# circuit.net
KiCad netlist of a schematic drawn in Altium Designer
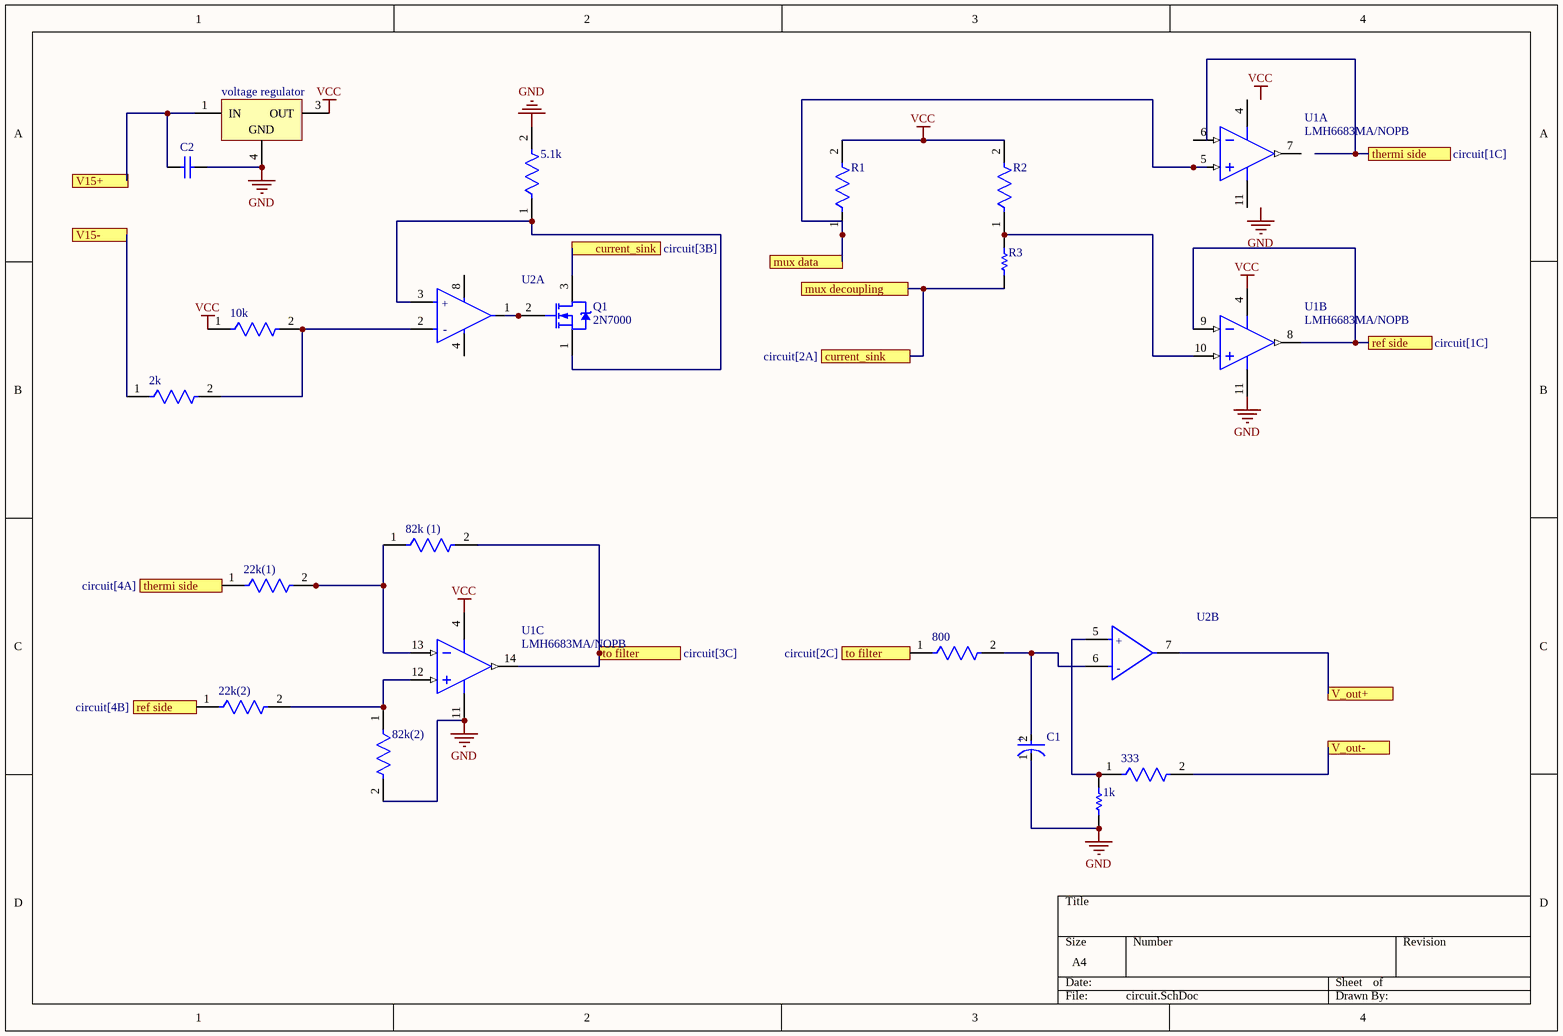
[diagram p0: circuit.SchDoc]

(export (version "E")
  (design (tool "Eeschema 10.0.6"))
  (components
    (comp (ref "1k")
      (value "CRCW12101K00FKEAHP")
      (footprint "RESC3225X60X45NL20T20")
      (fields (field (name "MANUFACTURER") "Vishay Dale"))
      (libsource (lib "Altium Content Vault") (part "RES"))
    )
    (comp (ref "2k")
      (value "CRCW12062K00FKEA")
      (footprint "FP-CRCW1206-e3-IPC_A")
      (description "RES Thick Film, 2kΩ, 1%, 0.25W, 100ppm/°C, 1206")
      (fields (field (name "TOLERANCE") "1%"))
      (libsource (lib "Altium Content Vault") (part "1029c3af85768c4190bb7ad29bc67b5"))
    )
    (comp (ref "5.1k")
      (value "CRCW12065K10FKEA")
      (footprint "FP-CRCW1206-e3-IPC_C")
      (description "RES Thick Film, 5.1kΩ, 1%, 0.25W, 100ppm/°C, 1206")
      (fields (field (name "TOLERANCE") "1%"))
      (libsource (lib "Altium Content Vault") (part "1029c3af85768c4190bb7ad29bc67b5"))
    )
    (comp (ref "10k")
      (value "CRCW120610K0FKEA")
      (footprint "FP-CRCW1206-e3-IPC_C")
      (description "RES Thick Film, 10kΩ, 1%, 0.25W, 100ppm/°C, 1206")
      (fields (field (name "TOLERANCE") "1%"))
      (libsource (lib "Altium Content Vault") (part "1029c3af85768c4190bb7ad29bc67b5"))
    )
    (comp (ref "22k(1)")
      (value "CRCW120622K0FKEA")
      (footprint "FP-CRCW1206-e3-IPC_A")
      (description "RES Thick Film, 22kΩ, 1%, 0.25W, 100ppm/°C, 1206")
      (fields (field (name "TOLERANCE") "1%"))
      (libsource (lib "Altium Content Vault") (part "1029c3af85768c4190bb7ad29bc67b5"))
    )
    (comp (ref "22k(2)")
      (value "CRCW120622K0FKEA")
      (footprint "FP-CRCW1206-e3-IPC_A")
      (description "RES Thick Film, 22kΩ, 1%, 0.25W, 100ppm/°C, 1206")
      (fields (field (name "TOLERANCE") "1%"))
      (libsource (lib "Altium Content Vault") (part "1029c3af85768c4190bb7ad29bc67b5"))
    )
    (comp (ref "82k (1)")
      (value "CRCW120682K0FKEA")
      (footprint "FP-CRCW1206-e3-IPC_B")
      (description "RES Thick Film, 82kΩ, 1%, 0.25W, 100ppm/°C, 1206")
      (fields (field (name "TOLERANCE") "1%"))
      (libsource (lib "Altium Content Vault") (part "1029c3af85768c4190bb7ad29bc67b5"))
    )
    (comp (ref "82k(2)")
      (value "CRCW120682K0FKEA")
      (footprint "FP-CRCW1206-e3-IPC_B")
      (description "RES Thick Film, 82kΩ, 1%, 0.25W, 100ppm/°C, 1206")
      (fields (field (name "TOLERANCE") "1%"))
      (libsource (lib "Altium Content Vault") (part "1029c3af85768c4190bb7ad29bc67b5"))
    )
    (comp (ref "333")
      (value "CRCW0603330RFKEAHP")
      (footprint "FP-CRCW0603-HPe3-IPC_C")
      (description "RES Thick Film, 330Ω, 1%, 0.33W, 100ppm/°C, 0603")
      (fields (field (name "TOLERANCE") "1%"))
      (libsource (lib "Altium Content Vault") (part "1029c3af85768c4190bb7ad29bc67b5"))
    )
    (comp (ref "800")
      (value "MCA12060D8000BP500")
      (footprint "FP-MCA1206-IPC_C")
      (description "Res MC Precision Thin Film 1206 800Ω 0.1% 0.25W ±25ppm/°C Molded Paper T/R")
      (fields (field (name "TOLERANCE") "0.1%"))
      (libsource (lib "Altium Content Vault") (part "1029c3af85768c4190bb7ad29bc67b5"))
    )
    (comp (ref "C1")
      (value "TAJA106K016RNJ")
      (footprint "FP-TAJA-MFG")
      (description "10uF 16V  ±10% 3Ω 1206  SMD Tantalum Capacitor")
      (fields (field (name "VOLTAGE") "16V") (field (name "TOLERANCE") "10%"))
      (libsource (lib "Altium Content Vault") (part "203bc49f2ac43e59fd269a8c329ed05"))
    )
    (comp (ref "C2")
      (value "GRM188R61E105KA12D")
      (footprint "CAPC1608X90X35LL10T15")
      (fields (field (name "MANUFACTURER") "Murata"))
      (libsource (lib "Altium Content Vault") (part "CAP"))
    )
    (comp (ref "Q1")
      (value "2N7000")
      (footprint "ONSC-TO-92-3-29-11")
      (description "Small Signal MOSFET, 200 mA, 60 V, N-Channel, 3-Pin TO-92, Bulk Box")
      (fields (field (name "MANUFACTURER") "On Semiconductor"))
      (libsource (lib "Altium Content Vault") (part "ONSC-NMOS-S1G2D3-3"))
    )
    (comp (ref "R1")
      (value "CRCW120633K0FKEA")
      (footprint "FP-CRCW1206-e3-IPC_B")
      (description "RES Thick Film, 33kΩ, 1%, 0.25W, 100ppm/°C, 1206")
      (fields (field (name "TOLERANCE") "1%"))
      (libsource (lib "Altium Content Vault") (part "1029c3af85768c4190bb7ad29bc67b5"))
    )
    (comp (ref "R2")
      (value "CRCW120633K0FKEA")
      (footprint "FP-CRCW1206-e3-IPC_B")
      (description "RES Thick Film, 33kΩ, 1%, 0.25W, 100ppm/°C, 1206")
      (fields (field (name "TOLERANCE") "1%"))
      (libsource (lib "Altium Content Vault") (part "1029c3af85768c4190bb7ad29bc67b5"))
    )
    (comp (ref "R3")
      (value "CRCW120615K0FKEA")
      (footprint "RESC3216X60X45LL10T20")
      (fields (field (name "MANUFACTURER") "Vishay Dale"))
      (libsource (lib "Altium Content Vault") (part "RES"))
    )
    (comp (ref "U1")
      (value "LMH6683MA/NOPB")
      (footprint "D0014A_M")
      (description "190MHz Single Supply, Dual and Triple Operational Amplifiers, 14-pin Narrow SOIC, Pb-Free")
      (fields (field (name "MANUFACTURER") "Texas Instruments"))
      (libsource (lib "Altium Content Vault") (part "AMP-OPA-LMH6683-14"))
    )
    (comp (ref "U2")
      (value "LM2904DGKR")
      (footprint "FP-DGK0008A-IPC_B")
      (description "IC OPAMP GP 2 CIRCUIT 8VSSOP")
      (libsource (lib "Altium Content Vault") (part "2a1159f5a9c9187fae0bca0d6f85a37"))
    )
    (comp (ref "voltage regulator")
      (value "L7812CD2T-TR")
      (footprint "TO-263_M")
      (description "Positive Voltage Regulator, 3-Pin D2PAK, Tape and Reel")
      (libsource (lib "Altium Content Vault") (part "PM-REG-L4940-SOT3"))
    )
  )
  (nets
    (net (code "2") (name "/V15-") (class "Default")
      (node (ref "2k") (pin "1") (pinfunction "1_1") (pintype "passive"))
    )
    (net (code "3") (name "/V_out+") (class "Default")
      (node (ref "U2") (pin "7") (pinfunction "OUT2_7") (pintype "passive"))
    )
    (net (code "4") (name "/V_out-") (class "Default")
      (node (ref "333") (pin "2") (pinfunction "2_2") (pintype "passive"))
    )
    (net (code "5") (name "/current_sink") (class "Default")
      (node (ref "Q1") (pin "3") (pinfunction "D_3") (pintype "passive"))
      (node (ref "R3") (pin "1") (pinfunction "1_1") (pintype "passive"))
    )
    (net (code "6") (name "/mux data") (class "Default")
      (node (ref "R1") (pin "1") (pinfunction "1_1") (pintype "passive"))
      (node (ref "U1") (pin "5") (pinfunction "IN1+_5") (pintype "input"))
    )
    (net (code "7") (name "/ref side") (class "Default")
      (node (ref "22k(2)") (pin "1") (pinfunction "1_1") (pintype "passive"))
      (node (ref "U1") (pin "8") (pinfunction "OUT2_8") (pintype "output"))
      (node (ref "U1") (pin "9") (pinfunction "IN2-_9") (pintype "input"))
    )
    (net (code "8") (name "/thermi side") (class "Default")
      (node (ref "22k(1)") (pin "1") (pinfunction "1_1") (pintype "passive"))
    )
    (net (code "9") (name "/to filter") (class "Default")
      (node (ref "800") (pin "1") (pinfunction "1_1") (pintype "passive"))
      (node (ref "82k (1)") (pin "2") (pinfunction "2_2") (pintype "passive"))
      (node (ref "U1") (pin "14") (pinfunction "OUT3_14") (pintype "output"))
    )
    (net (code "10") (name "GND") (class "Default")
      (node (ref "1k") (pin "1") (pinfunction "1_1") (pintype "passive"))
      (node (ref "5.1k") (pin "2") (pinfunction "2_2") (pintype "passive"))
      (node (ref "82k(2)") (pin "2") (pinfunction "2_2") (pintype "passive"))
      (node (ref "C1") (pin "1") (pinfunction "C_1") (pintype "passive"))
      (node (ref "C2") (pin "2") (pinfunction "2_2") (pintype "passive"))
      (node (ref "U1") (pin "11") (pinfunction "V-_11") (pintype "power_in"))
      (node (ref "voltage regulator") (pin "4") (pinfunction "GND_4") (pintype "power_in"))
    )
    (net (code "11") (name "Net-(C1-A)") (class "Default")
      (node (ref "800") (pin "2") (pinfunction "2_2") (pintype "passive"))
      (node (ref "C1") (pin "2") (pinfunction "A_2") (pintype "passive"))
      (node (ref "U2") (pin "6") (pinfunction "IN2-_6") (pintype "tri_state"))
    )
    (net (code "12") (name "Net-(Q1-G)") (class "Default")
      (node (ref "Q1") (pin "2") (pinfunction "G_2") (pintype "passive"))
      (node (ref "U2") (pin "1") (pinfunction "OUT1_1") (pintype "passive"))
    )
    (net (code "13") (name "Net-(Q1-S)") (class "Default")
      (node (ref "5.1k") (pin "1") (pinfunction "1_1") (pintype "passive"))
      (node (ref "Q1") (pin "1") (pinfunction "S_1") (pintype "passive"))
      (node (ref "U2") (pin "3") (pinfunction "IN1+_3") (pintype "tri_state"))
    )
    (net (code "14") (name "Net-(U1B-IN2+)") (class "Default")
      (node (ref "R2") (pin "1") (pinfunction "1_1") (pintype "passive"))
      (node (ref "R3") (pin "2") (pinfunction "2_2") (pintype "passive"))
      (node (ref "U1") (pin "10") (pinfunction "IN2+_10") (pintype "input"))
    )
    (net (code "15") (name "Net-(U1C-IN3+)") (class "Default")
      (node (ref "22k(2)") (pin "2") (pinfunction "2_2") (pintype "passive"))
      (node (ref "82k(2)") (pin "1") (pinfunction "1_1") (pintype "passive"))
      (node (ref "U1") (pin "12") (pinfunction "IN3+_12") (pintype "input"))
    )
    (net (code "16") (name "Net-(U1C-IN3-)") (class "Default")
      (node (ref "22k(1)") (pin "2") (pinfunction "2_2") (pintype "passive"))
      (node (ref "82k (1)") (pin "1") (pinfunction "1_1") (pintype "passive"))
      (node (ref "U1") (pin "13") (pinfunction "IN3-_13") (pintype "input"))
    )
    (net (code "17") (name "Net-(U2A-IN1-)") (class "Default")
      (node (ref "10k") (pin "2") (pinfunction "2_2") (pintype "passive"))
      (node (ref "2k") (pin "2") (pinfunction "2_2") (pintype "passive"))
      (node (ref "U2") (pin "2") (pinfunction "IN1-_2") (pintype "tri_state"))
    )
    (net (code "18") (name "Net-(U2B-IN2+)") (class "Default")
      (node (ref "1k") (pin "2") (pinfunction "2_2") (pintype "passive"))
      (node (ref "333") (pin "1") (pinfunction "1_1") (pintype "passive"))
      (node (ref "U2") (pin "5") (pinfunction "IN2+_5") (pintype "tri_state"))
    )
    (net (code "19") (name "Net-(voltage regulator-IN)") (class "Default")
      (node (ref "C2") (pin "1") (pinfunction "1_1") (pintype "passive"))
      (node (ref "voltage regulator") (pin "1") (pinfunction "IN_1") (pintype "power_in"))
    )
    (net (code "20") (name "VCC") (class "Default")
      (node (ref "10k") (pin "1") (pinfunction "1_1") (pintype "passive"))
      (node (ref "R1") (pin "2") (pinfunction "2_2") (pintype "passive"))
      (node (ref "R2") (pin "2") (pinfunction "2_2") (pintype "passive"))
      (node (ref "U1") (pin "4") (pinfunction "V+_4") (pintype "power_in"))
      (node (ref "voltage regulator") (pin "3") (pinfunction "OUT_3") (pintype "power_in"))
    )
    (net (code "21") (name "unconnected-(U1A-IN1--Pad6)") (class "Default")
      (node (ref "U1") (pin "6") (pinfunction "IN1-_6") (pintype "input"))
    )
    (net (code "22") (name "unconnected-(U1A-OUT1-Pad7)") (class "Default")
      (node (ref "U1") (pin "7") (pinfunction "OUT1_7") (pintype "output"))
    )
    (net (code "23") (name "unconnected-(U1A-V+-Pad4)") (class "Default")
      (node (ref "U1") (pin "4") (pinfunction "V+_4") (pintype "power_in"))
    )
    (net (code "24") (name "unconnected-(U1A-V--Pad11)") (class "Default")
      (node (ref "U1") (pin "11") (pinfunction "V-_11") (pintype "power_in"))
    )
    (net (code "25") (name "unconnected-(U2A-V+-Pad8)") (class "Default")
      (node (ref "U2") (pin "8") (pinfunction "V+_8") (pintype "power_in"))
    )
    (net (code "26") (name "unconnected-(U2A-V--Pad4)") (class "Default")
      (node (ref "U2") (pin "4") (pinfunction "V-_4") (pintype "power_in"))
    )
  )
)
